# parallel_R_LED.net
KiCad netlist of a schematic drawn in EAGLE
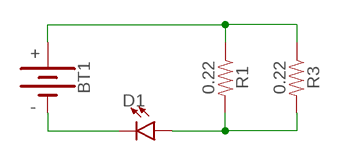
[diagram p0: schematic, sheet 1]

(export (version "E")
  (design (tool "Eeschema 10.0.6"))
  (components
    (comp (ref "BT1")
      (value "BATTERY-9V")
      (footprint "eagle-import:BATTCON_9V")
      (libsource (lib "eagle-import") (part "BATTERY-9V"))
    )
    (comp (ref "D1")
      (value "LED5MM")
      (footprint "eagle-import:LED_5MM")
      (libsource (lib "eagle-import") (part "LED5MM"))
    )
    (comp (ref "R1")
      (value "0.22")
      (footprint "eagle-import:0805")
      (libsource (lib "eagle-import") (part "0.22OHM-0805-1/4W-1%"))
    )
    (comp (ref "R3")
      (value "0.22")
      (footprint "eagle-import:0805")
      (libsource (lib "eagle-import") (part "0.22OHM-0805-1/4W-1%"))
    )
  )
  (nets
    (net (code "1") (name "Net-(BT1-Pad+)") (class "Default")
      (node (ref "BT1") (pin "+") (pinfunction "+_+") (pintype "power_in"))
      (node (ref "R1") (pin "1") (pinfunction "1_1") (pintype "passive"))
      (node (ref "R3") (pin "1") (pinfunction "1_1") (pintype "passive"))
    )
    (net (code "2") (name "Net-(D1-C)") (class "Default")
      (node (ref "BT1") (pin "-") (pinfunction "-_-") (pintype "power_in"))
      (node (ref "D1") (pin "K") (pinfunction "C_K") (pintype "passive"))
    )
    (net (code "3") (name "Net-(D1-PadA)") (class "Default")
      (node (ref "D1") (pin "A") (pinfunction "A_A") (pintype "passive"))
      (node (ref "R1") (pin "2") (pinfunction "2_2") (pintype "passive"))
      (node (ref "R3") (pin "2") (pinfunction "2_2") (pintype "passive"))
    )
  )
)
